# Tracksoar_v2.net
KiCad netlist of a schematic drawn in EAGLE
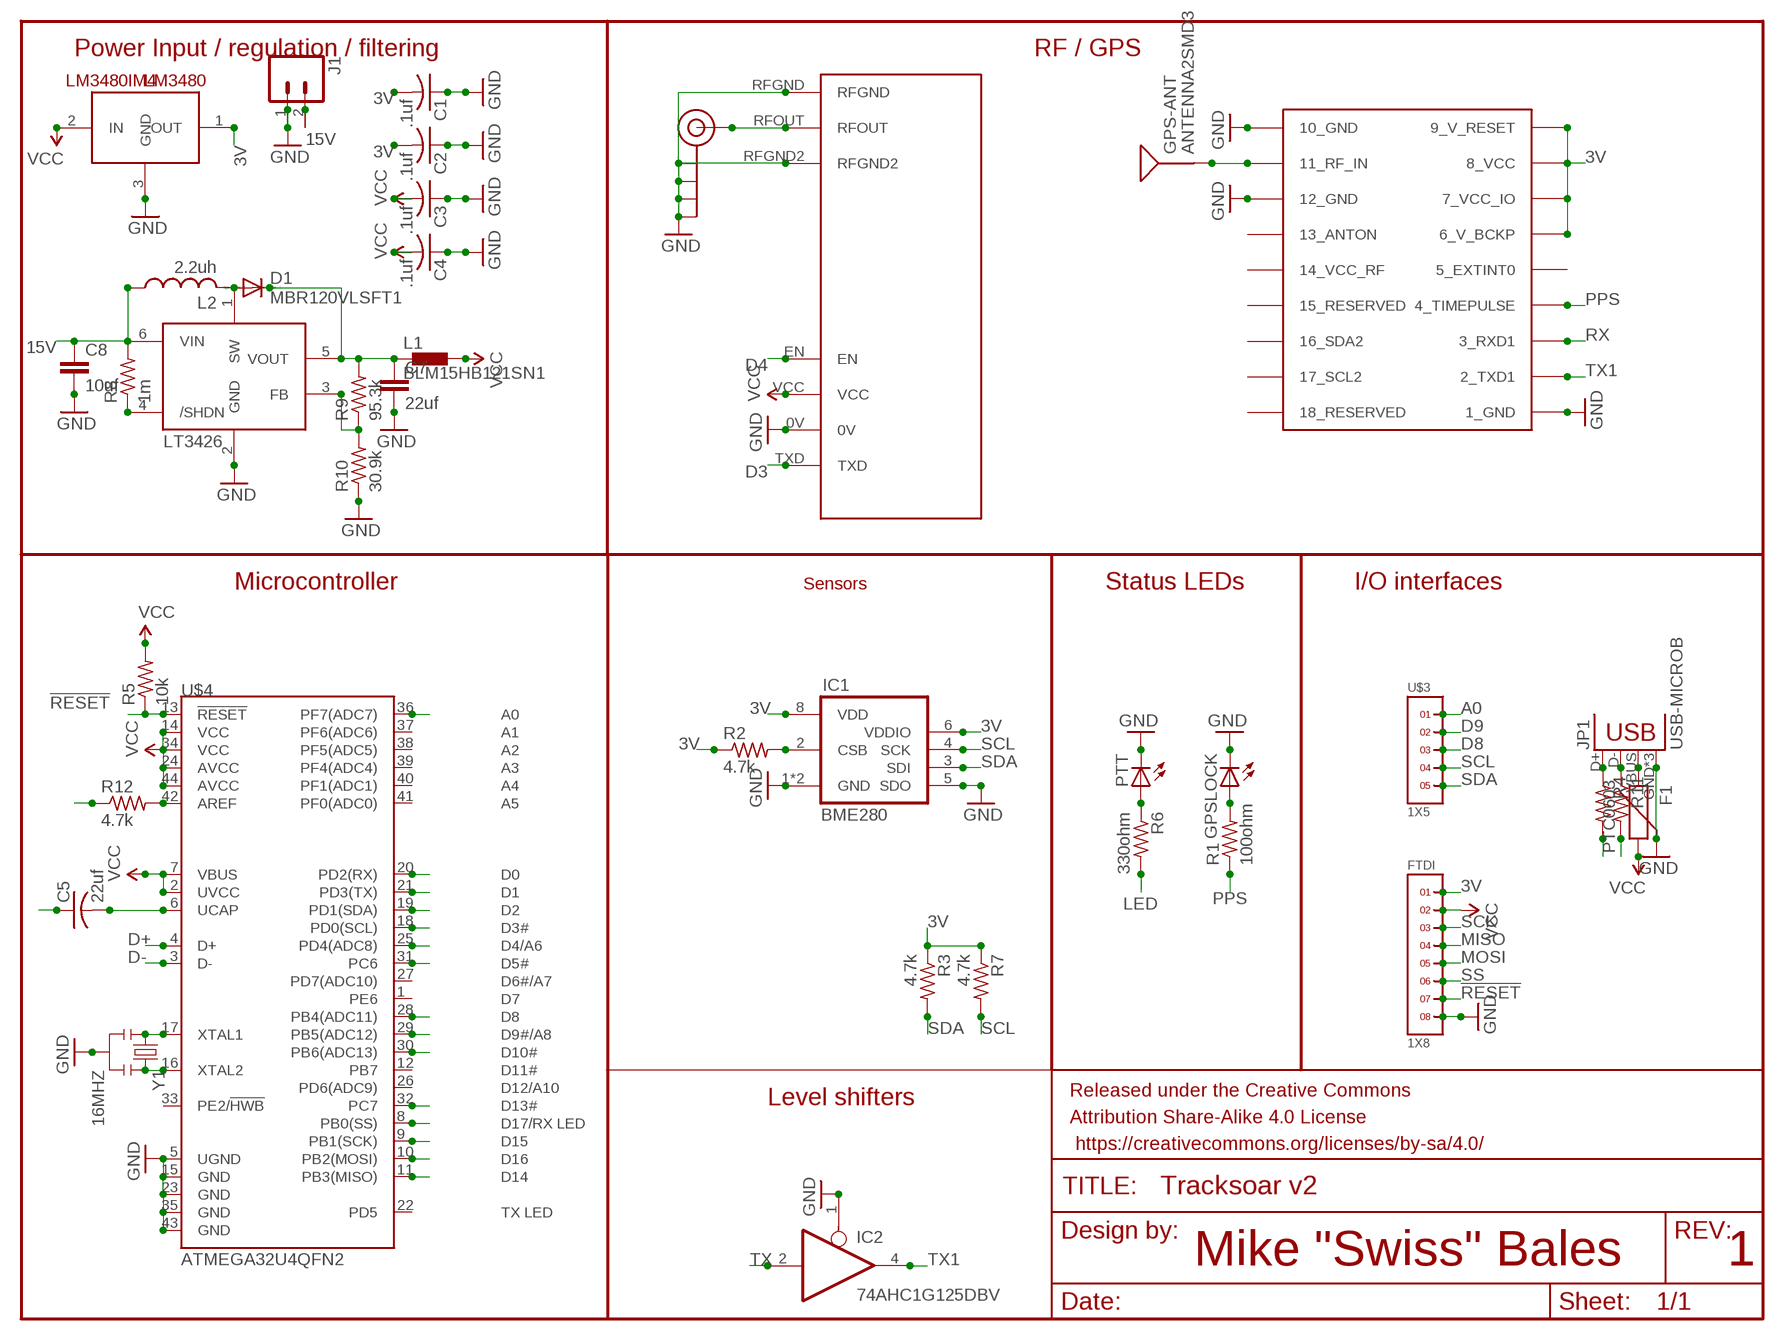
[diagram p0: schematic, sheet 1]

(export (version "E")
  (design (tool "Eeschema 10.0.6"))
  (components
    (comp (ref "C1")
      (value ".1uf")
      (footprint "eagle-import:C0402")
      (libsource (lib "eagle-import") (part "C-USC0402"))
    )
    (comp (ref "C2")
      (value ".1uf")
      (footprint "eagle-import:C0402")
      (libsource (lib "eagle-import") (part "C-USC0402"))
    )
    (comp (ref "C3")
      (value ".1uf")
      (footprint "eagle-import:C0402")
      (libsource (lib "eagle-import") (part "C-USC0402"))
    )
    (comp (ref "C4")
      (value ".1uf")
      (footprint "eagle-import:C0402")
      (libsource (lib "eagle-import") (part "C-USC0402"))
    )
    (comp (ref "C5")
      (value "22uf")
      (footprint "eagle-import:C0402")
      (libsource (lib "eagle-import") (part "rcl_C-USC0402"))
    )
    (comp (ref "C7")
      (value "22uf")
      (footprint "eagle-import:0805")
      (libsource (lib "eagle-import") (part "CAP0805"))
    )
    (comp (ref "C8")
      (value "10uf")
      (footprint "eagle-import:0805")
      (libsource (lib "eagle-import") (part "CAP0805"))
    )
    (comp (ref "D1")
      (value "MBR120VLSFT1")
      (footprint "eagle-import:SOD123")
      (libsource (lib "eagle-import") (part "DIODE-SOD123"))
    )
    (comp (ref "F1")
      (value "PTC0603")
      (footprint "eagle-import:0603")
      (libsource (lib "eagle-import") (part "PTC0603"))
    )
    (comp (ref "FRAME1")
      (value "FRAME-LETTER")
      (footprint "eagle-import:CREATIVE_COMMONS")
      (libsource (lib "eagle-import") (part "FRAME-LETTER"))
    )
    (comp (ref "FTDI")
      (value "1X8")
      (footprint "eagle-import:1X8")
      (libsource (lib "eagle-import") (part "1X8"))
    )
    (comp (ref "GPS-ANT")
      (value "ANTENNA2SMD3")
      (footprint "eagle-import:ANTENNA-CHIP4")
      (libsource (lib "eagle-import") (part "ANTENNA2SMD3"))
    )
    (comp (ref "GPSLOCK")
      (value "LEDCHIP-LED0603")
      (footprint "eagle-import:CHIP-LED0603")
      (libsource (lib "eagle-import") (part "LEDCHIP-LED0603"))
    )
    (comp (ref "IC1")
      (value "BME280")
      (footprint "eagle-import:BME280")
      (libsource (lib "eagle-import") (part "BME280"))
    )
    (comp (ref "IC2")
      (value "74AHC1G125DBV")
      (footprint "eagle-import:SOT23-5")
      (libsource (lib "eagle-import") (part "741G125DBVAHC"))
    )
    (comp (ref "J$1")
      (value "SMA_EDGE")
      (footprint "eagle-import:SMA-EDGE")
      (libsource (lib "eagle-import") (part "SMA_EDGE"))
    )
    (comp (ref "J1")
      (value "M02JST-PTH-2")
      (footprint "eagle-import:JST-2-PTH")
      (libsource (lib "eagle-import") (part "M02JST-PTH-2"))
    )
    (comp (ref "JP1")
      (value "USB-MICROB")
      (footprint "eagle-import:USB-MICROB")
      (libsource (lib "eagle-import") (part "USB-MICROB"))
    )
    (comp (ref "L1")
      (value "BLM15HB121SN1")
      (footprint "eagle-import:0402")
      (libsource (lib "eagle-import") (part "BLM15HB121SN1"))
    )
    (comp (ref "L2")
      (value "2.2uh")
      (footprint "eagle-import:L1812")
      (libsource (lib "eagle-import") (part "L-USL1812"))
    )
    (comp (ref "LM3480")
      (value "LM3480IM4")
      (footprint "eagle-import:SOT23-3")
      (libsource (lib "eagle-import") (part "LM3480IM4"))
    )
    (comp (ref "LT3426")
      (value "LT3426")
      (footprint "eagle-import:SOT23-6")
      (libsource (lib "eagle-import") (part "LT3426"))
    )
    (comp (ref "PTT")
      (value "LEDCHIP-LED0603")
      (footprint "eagle-import:CHIP-LED0603")
      (libsource (lib "eagle-import") (part "LEDCHIP-LED0603"))
    )
    (comp (ref "R1")
      (value "100ohm")
      (footprint "eagle-import:R0402")
      (libsource (lib "eagle-import") (part "R-US_R0402"))
    )
    (comp (ref "R2")
      (value "4.7k")
      (footprint "eagle-import:R0402")
      (libsource (lib "eagle-import") (part "R-US_R0402"))
    )
    (comp (ref "R3")
      (value "4.7k")
      (footprint "eagle-import:R0402")
      (libsource (lib "eagle-import") (part "R-US_R0402"))
    )
    (comp (ref "R4")
      (value "R-US_R0402")
      (footprint "eagle-import:R0402")
      (libsource (lib "eagle-import") (part "R-US_R0402"))
    )
    (comp (ref "R5")
      (value "10k")
      (footprint "eagle-import:R0402")
      (libsource (lib "eagle-import") (part "R-US_R0402"))
    )
    (comp (ref "R6")
      (value "330ohm")
      (footprint "eagle-import:R0402")
      (libsource (lib "eagle-import") (part "R-US_R0402"))
    )
    (comp (ref "R7")
      (value "4.7k")
      (footprint "eagle-import:R0402")
      (libsource (lib "eagle-import") (part "R-US_R0402"))
    )
    (comp (ref "R8")
      (value "1m")
      (footprint "eagle-import:R0402")
      (libsource (lib "eagle-import") (part "R-US_R0402"))
    )
    (comp (ref "R9")
      (value "95.3k")
      (footprint "eagle-import:R0402")
      (libsource (lib "eagle-import") (part "R-US_R0402"))
    )
    (comp (ref "R10")
      (value "30.9k")
      (footprint "eagle-import:R0402")
      (libsource (lib "eagle-import") (part "R-US_R0402"))
    )
    (comp (ref "R11")
      (value "R-US_R0402")
      (footprint "eagle-import:R0402")
      (libsource (lib "eagle-import") (part "R-US_R0402"))
    )
    (comp (ref "R12")
      (value "4.7k")
      (footprint "eagle-import:R0402")
      (libsource (lib "eagle-import") (part "R-US_R0402"))
    )
    (comp (ref "U$1")
      (value "UBLOX_MAX")
      (footprint "eagle-import:UBLOX_MAX")
      (libsource (lib "eagle-import") (part "UBLOX_MAX"))
    )
    (comp (ref "U$2")
      (value "RADIOMETRIX-HX1")
      (footprint "eagle-import:RADIOMETRIX-HX1")
      (libsource (lib "eagle-import") (part "RADIOMETRIX-HX1"))
    )
    (comp (ref "U$3")
      (value "1X5")
      (footprint "eagle-import:1X5")
      (libsource (lib "eagle-import") (part "1X5"))
    )
    (comp (ref "U$4")
      (value "ATMEGA32U4QFN2")
      (footprint "eagle-import:QFN-44-NOPAD")
      (libsource (lib "eagle-import") (part "ATMEGA32U4QFN2"))
    )
    (comp (ref "Y1")
      (value "16MHZ")
      (footprint "eagle-import:RESONATOR-SMD")
      (libsource (lib "eagle-import") (part "RESONATOR16MHZ"))
    )
  )
  (nets
    (net (code "1") (name "/3V") (class "Default")
      (node (ref "C1") (pin "2") (pinfunction "2_2") (pintype "passive"))
      (node (ref "C2") (pin "2") (pinfunction "2_2") (pintype "passive"))
      (node (ref "FTDI") (pin "1") (pinfunction "1_1") (pintype "bidirectional"))
      (node (ref "IC1") (pin "6") (pinfunction "VDDIO_6") (pintype "power_in"))
      (node (ref "IC1") (pin "8") (pinfunction "VDD_8") (pintype "power_in"))
      (node (ref "LM3480") (pin "1") (pinfunction "OUT_1") (pintype "bidirectional"))
      (node (ref "R2") (pin "1") (pinfunction "1_1") (pintype "passive"))
      (node (ref "R3") (pin "1") (pinfunction "1_1") (pintype "passive"))
      (node (ref "R7") (pin "1") (pinfunction "1_1") (pintype "passive"))
      (node (ref "U$1") (pin "6_V_BCKP") (pinfunction "6_V_BCKP_6_V_BCKP") (pintype "bidirectional"))
      (node (ref "U$1") (pin "7_VCC_IO") (pinfunction "7_VCC_IO_7_VCC_IO") (pintype "power_in"))
      (node (ref "U$1") (pin "8_VCC") (pinfunction "8_VCC_8_VCC") (pintype "power_in"))
      (node (ref "U$1") (pin "9_V_RESET") (pinfunction "9_V_RESET_9_V_RESET") (pintype "power_in"))
    )
    (net (code "2") (name "/15V") (class "Default")
      (node (ref "C8") (pin "1") (pinfunction "1_1") (pintype "passive"))
      (node (ref "J1") (pin "2") (pinfunction "2_2") (pintype "passive"))
      (node (ref "L2") (pin "1") (pinfunction "1_1") (pintype "passive"))
      (node (ref "LT3426") (pin "6") (pinfunction "VIN_6") (pintype "input"))
      (node (ref "R12") (pin "1") (pinfunction "1_1") (pintype "passive"))
      (node (ref "R8") (pin "2") (pinfunction "2_2") (pintype "passive"))
    )
    (net (code "3") (name "/A0") (class "Default")
      (node (ref "U$3") (pin "1") (pinfunction "1_1") (pintype "bidirectional"))
      (node (ref "U$4") (pin "36") (pinfunction "PF7(ADC7)_36") (pintype "bidirectional"))
    )
    (net (code "4") (name "/D+") (class "Default")
      (node (ref "R4") (pin "2") (pinfunction "2_2") (pintype "passive"))
      (node (ref "U$4") (pin "4") (pinfunction "D+_4") (pintype "bidirectional"))
    )
    (net (code "5") (name "/D-") (class "Default")
      (node (ref "R11") (pin "2") (pinfunction "2_2") (pintype "passive"))
      (node (ref "U$4") (pin "3") (pinfunction "D-_3") (pintype "bidirectional"))
    )
    (net (code "6") (name "/D3") (class "Default")
      (node (ref "U$2") (pin "TXD") (pinfunction "TXD_TXD") (pintype "bidirectional"))
      (node (ref "U$4") (pin "30") (pinfunction "PB6(ADC13)_30") (pintype "bidirectional"))
    )
    (net (code "7") (name "/D4") (class "Default")
      (node (ref "U$2") (pin "EN") (pinfunction "EN_EN") (pintype "bidirectional"))
      (node (ref "U$4") (pin "25") (pinfunction "PD4(ADC8)_25") (pintype "bidirectional"))
    )
    (net (code "8") (name "/D8") (class "Default")
      (node (ref "U$3") (pin "3") (pinfunction "3_3") (pintype "bidirectional"))
      (node (ref "U$4") (pin "28") (pinfunction "PB4(ADC11)_28") (pintype "bidirectional"))
    )
    (net (code "9") (name "/D9") (class "Default")
      (node (ref "U$3") (pin "2") (pinfunction "2_2") (pintype "bidirectional"))
      (node (ref "U$4") (pin "29") (pinfunction "PB5(ADC12)_29") (pintype "bidirectional"))
    )
    (net (code "10") (name "/LED") (class "Default")
      (node (ref "R6") (pin "2") (pinfunction "2_2") (pintype "passive"))
      (node (ref "U$4") (pin "31") (pinfunction "PC6_31") (pintype "bidirectional"))
    )
    (net (code "11") (name "/MISO") (class "Default")
      (node (ref "FTDI") (pin "4") (pinfunction "4_4") (pintype "bidirectional"))
      (node (ref "U$4") (pin "11") (pinfunction "PB3(MISO)_11") (pintype "bidirectional"))
    )
    (net (code "12") (name "/MOSI") (class "Default")
      (node (ref "FTDI") (pin "5") (pinfunction "5_5") (pintype "bidirectional"))
      (node (ref "U$4") (pin "10") (pinfunction "PB2(MOSI)_10") (pintype "bidirectional"))
    )
    (net (code "13") (name "/PPS") (class "Default")
      (node (ref "R1") (pin "1") (pinfunction "1_1") (pintype "passive"))
      (node (ref "U$1") (pin "4_TIMEPULSE") (pinfunction "4_TIMEPULSE_4_TIMEPULSE") (pintype "bidirectional"))
    )
    (net (code "14") (name "/RX") (class "Default")
      (node (ref "U$1") (pin "3_RXD1") (pinfunction "3_RXD1_3_RXD1") (pintype "bidirectional"))
      (node (ref "U$4") (pin "21") (pinfunction "PD3(TX)_21") (pintype "bidirectional"))
    )
    (net (code "15") (name "/SCK") (class "Default")
      (node (ref "FTDI") (pin "3") (pinfunction "3_3") (pintype "bidirectional"))
      (node (ref "U$4") (pin "9") (pinfunction "PB1(SCK)_9") (pintype "bidirectional"))
    )
    (net (code "16") (name "/SCL") (class "Default")
      (node (ref "IC1") (pin "4") (pinfunction "SCK_4") (pintype "bidirectional"))
      (node (ref "R7") (pin "2") (pinfunction "2_2") (pintype "passive"))
      (node (ref "U$3") (pin "4") (pinfunction "4_4") (pintype "bidirectional"))
      (node (ref "U$4") (pin "18") (pinfunction "PD0(SCL)_18") (pintype "bidirectional"))
    )
    (net (code "17") (name "/SDA") (class "Default")
      (node (ref "IC1") (pin "3") (pinfunction "SDI_3") (pintype "bidirectional"))
      (node (ref "R3") (pin "2") (pinfunction "2_2") (pintype "passive"))
      (node (ref "U$3") (pin "5") (pinfunction "5_5") (pintype "bidirectional"))
      (node (ref "U$4") (pin "19") (pinfunction "PD1(SDA)_19") (pintype "bidirectional"))
    )
    (net (code "18") (name "/SS") (class "Default")
      (node (ref "FTDI") (pin "6") (pinfunction "6_6") (pintype "bidirectional"))
      (node (ref "U$4") (pin "8") (pinfunction "PB0(SS)_8") (pintype "bidirectional"))
    )
    (net (code "19") (name "/TX") (class "Default")
      (node (ref "IC2") (pin "2") (pinfunction "I_2") (pintype "input"))
      (node (ref "U$4") (pin "20") (pinfunction "PD2(RX)_20") (pintype "bidirectional"))
    )
    (net (code "20") (name "/TX1") (class "Default")
      (node (ref "IC2") (pin "4") (pinfunction "O_4") (pintype "tri_state"))
      (node (ref "U$1") (pin "2_TXD1") (pinfunction "2_TXD1_2_TXD1") (pintype "bidirectional"))
    )
    (net (code "21") (name "/~{RESET}") (class "Default")
      (node (ref "FTDI") (pin "7") (pinfunction "7_7") (pintype "bidirectional"))
      (node (ref "R5") (pin "1") (pinfunction "1_1") (pintype "passive"))
      (node (ref "U$4") (pin "13") (pinfunction "~{RESET}_13") (pintype "bidirectional"))
    )
    (net (code "22") (name "GND") (class "Default")
      (node (ref "C1") (pin "1") (pinfunction "1_1") (pintype "passive"))
      (node (ref "C2") (pin "1") (pinfunction "1_1") (pintype "passive"))
      (node (ref "C3") (pin "1") (pinfunction "1_1") (pintype "passive"))
      (node (ref "C4") (pin "1") (pinfunction "1_1") (pintype "passive"))
      (node (ref "C5") (pin "1") (pinfunction "1_1") (pintype "passive"))
      (node (ref "C7") (pin "2") (pinfunction "2_2") (pintype "passive"))
      (node (ref "C8") (pin "2") (pinfunction "2_2") (pintype "passive"))
      (node (ref "FTDI") (pin "8") (pinfunction "8_8") (pintype "bidirectional"))
      (node (ref "GPSLOCK") (pin "C") (pinfunction "C_C") (pintype "passive"))
      (node (ref "IC1") (pin "1") (pinfunction "GND_1") (pintype "power_in"))
      (node (ref "IC1") (pin "5") (pinfunction "SDO_5") (pintype "input"))
      (node (ref "IC1") (pin "7") (pinfunction "GND_7") (pintype "power_in"))
      (node (ref "IC2") (pin "1") (pinfunction "OE_1") (pintype "input"))
      (node (ref "J$1") (pin "GND@0") (pinfunction "GND_GND@0") (pintype "bidirectional"))
      (node (ref "J$1") (pin "GND@1") (pinfunction "GND_GND@1") (pintype "bidirectional"))
      (node (ref "J$1") (pin "GND@2") (pinfunction "GND_GND@2") (pintype "bidirectional"))
      (node (ref "J$1") (pin "GND@3") (pinfunction "GND_GND@3") (pintype "bidirectional"))
      (node (ref "J1") (pin "1") (pinfunction "1_1") (pintype "passive"))
      (node (ref "JP1") (pin "GND") (pinfunction "GND_GND") (pintype "bidirectional"))
      (node (ref "JP1") (pin "MT1") (pinfunction "GND_MT1") (pintype "bidirectional"))
      (node (ref "JP1") (pin "MT2") (pinfunction "GND_MT2") (pintype "bidirectional"))
      (node (ref "LM3480") (pin "3") (pinfunction "GND_3") (pintype "bidirectional"))
      (node (ref "LT3426") (pin "2") (pinfunction "GND_2") (pintype "power_in"))
      (node (ref "PTT") (pin "C") (pinfunction "C_C") (pintype "passive"))
      (node (ref "R10") (pin "1") (pinfunction "1_1") (pintype "passive"))
      (node (ref "U$1") (pin "10_GND") (pinfunction "10_GND_10_GND") (pintype "power_in"))
      (node (ref "U$1") (pin "12_GND") (pinfunction "12_GND_12_GND") (pintype "power_in"))
      (node (ref "U$1") (pin "1_GND") (pinfunction "1_GND_1_GND") (pintype "power_in"))
      (node (ref "U$2") (pin "0V") (pinfunction "0V_0V") (pintype "bidirectional"))
      (node (ref "U$2") (pin "RFGND") (pinfunction "RFGND_RFGND") (pintype "bidirectional"))
      (node (ref "U$2") (pin "RFGND2") (pinfunction "RFGND2_RFGND2") (pintype "bidirectional"))
      (node (ref "U$4") (pin "15") (pinfunction "GND_15") (pintype "bidirectional"))
      (node (ref "U$4") (pin "23") (pinfunction "GND_23") (pintype "bidirectional"))
      (node (ref "U$4") (pin "35") (pinfunction "GND_35") (pintype "bidirectional"))
      (node (ref "U$4") (pin "43") (pinfunction "GND_43") (pintype "bidirectional"))
      (node (ref "U$4") (pin "5") (pinfunction "UGND_5") (pintype "bidirectional"))
      (node (ref "Y1") (pin "2") (pinfunction "2_2") (pintype "passive"))
    )
    (net (code "23") (name "Net-(F1-Pad1)") (class "Default")
      (node (ref "F1") (pin "1") (pinfunction "1_1") (pintype "bidirectional"))
      (node (ref "JP1") (pin "VBUS") (pinfunction "VBUS_VBUS") (pintype "bidirectional"))
    )
    (net (code "24") (name "Net-(GPS-ANT-SIGNAL)") (class "Default")
      (node (ref "GPS-ANT") (pin "SIG") (pinfunction "SIGNAL_SIG") (pintype "bidirectional"))
      (node (ref "U$1") (pin "11_RF_IN") (pinfunction "11_RF_IN_11_RF_IN") (pintype "bidirectional"))
    )
    (net (code "25") (name "Net-(GPSLOCK-PadA)") (class "Default")
      (node (ref "GPSLOCK") (pin "A") (pinfunction "A_A") (pintype "passive"))
      (node (ref "R1") (pin "2") (pinfunction "2_2") (pintype "passive"))
    )
    (net (code "26") (name "Net-(IC1-CSB)") (class "Default")
      (node (ref "IC1") (pin "2") (pinfunction "CSB_2") (pintype "input"))
      (node (ref "R2") (pin "2") (pinfunction "2_2") (pintype "passive"))
    )
    (net (code "27") (name "Net-(J$1-SIGNAL)") (class "Default")
      (node (ref "J$1") (pin "SIG") (pinfunction "SIGNAL_SIG") (pintype "bidirectional"))
      (node (ref "U$2") (pin "RFOUT") (pinfunction "RFOUT_RFOUT") (pintype "bidirectional"))
    )
    (net (code "28") (name "Net-(JP1-PadD+)") (class "Default")
      (node (ref "JP1") (pin "D+") (pinfunction "D+_D+") (pintype "bidirectional"))
      (node (ref "R4") (pin "1") (pinfunction "1_1") (pintype "passive"))
    )
    (net (code "29") (name "Net-(JP1-PadD-)") (class "Default")
      (node (ref "JP1") (pin "D-") (pinfunction "D-_D-") (pintype "bidirectional"))
      (node (ref "R11") (pin "1") (pinfunction "1_1") (pintype "passive"))
    )
    (net (code "30") (name "Net-(LT3426-FB)") (class "Default")
      (node (ref "LT3426") (pin "3") (pinfunction "FB_3") (pintype "input"))
      (node (ref "R10") (pin "2") (pinfunction "2_2") (pintype "passive"))
      (node (ref "R9") (pin "1") (pinfunction "1_1") (pintype "passive"))
    )
    (net (code "31") (name "Net-(LT3426-SW)") (class "Default")
      (node (ref "D1") (pin "A") (pinfunction "A_A") (pintype "passive"))
      (node (ref "L2") (pin "2") (pinfunction "2_2") (pintype "passive"))
      (node (ref "LT3426") (pin "1") (pinfunction "SW_1") (pintype "output"))
    )
    (net (code "32") (name "Net-(LT3426-VOUT)") (class "Default")
      (node (ref "C7") (pin "1") (pinfunction "1_1") (pintype "passive"))
      (node (ref "D1") (pin "C") (pinfunction "C_C") (pintype "passive"))
      (node (ref "L1") (pin "1") (pinfunction "1_1") (pintype "passive"))
      (node (ref "LT3426") (pin "5") (pinfunction "VOUT_5") (pintype "output"))
      (node (ref "R9") (pin "2") (pinfunction "2_2") (pintype "passive"))
    )
    (net (code "33") (name "Net-(LT3426-{slash}SHDN)") (class "Default")
      (node (ref "LT3426") (pin "4") (pinfunction "/SHDN_4") (pintype "input"))
      (node (ref "R8") (pin "1") (pinfunction "1_1") (pintype "passive"))
    )
    (net (code "34") (name "Net-(PTT-PadA)") (class "Default")
      (node (ref "PTT") (pin "A") (pinfunction "A_A") (pintype "passive"))
      (node (ref "R6") (pin "1") (pinfunction "1_1") (pintype "passive"))
    )
    (net (code "35") (name "Net-(U$4-AREF)") (class "Default")
      (node (ref "R12") (pin "2") (pinfunction "2_2") (pintype "passive"))
      (node (ref "U$4") (pin "42") (pinfunction "AREF_42") (pintype "bidirectional"))
    )
    (net (code "36") (name "Net-(U$4-UCAP)") (class "Default")
      (node (ref "C5") (pin "2") (pinfunction "2_2") (pintype "passive"))
      (node (ref "U$4") (pin "6") (pinfunction "UCAP_6") (pintype "bidirectional"))
    )
    (net (code "37") (name "Net-(U$4-XTAL1)") (class "Default")
      (node (ref "U$4") (pin "17") (pinfunction "XTAL1_17") (pintype "bidirectional"))
      (node (ref "Y1") (pin "1") (pinfunction "1_1") (pintype "passive"))
    )
    (net (code "38") (name "Net-(U$4-XTAL2)") (class "Default")
      (node (ref "U$4") (pin "16") (pinfunction "XTAL2_16") (pintype "bidirectional"))
      (node (ref "Y1") (pin "3") (pinfunction "3_3") (pintype "passive"))
    )
    (net (code "39") (name "VCC") (class "Default")
      (node (ref "C3") (pin "2") (pinfunction "2_2") (pintype "passive"))
      (node (ref "C4") (pin "2") (pinfunction "2_2") (pintype "passive"))
      (node (ref "F1") (pin "2") (pinfunction "2_2") (pintype "bidirectional"))
      (node (ref "FTDI") (pin "2") (pinfunction "2_2") (pintype "bidirectional"))
      (node (ref "L1") (pin "2") (pinfunction "2_2") (pintype "passive"))
      (node (ref "LM3480") (pin "2") (pinfunction "IN_2") (pintype "bidirectional"))
      (node (ref "R5") (pin "2") (pinfunction "2_2") (pintype "passive"))
      (node (ref "U$2") (pin "VCC") (pinfunction "VCC_VCC") (pintype "bidirectional"))
      (node (ref "U$4") (pin "14") (pinfunction "VCC_14") (pintype "bidirectional"))
      (node (ref "U$4") (pin "2") (pinfunction "UVCC_2") (pintype "bidirectional"))
      (node (ref "U$4") (pin "24") (pinfunction "AVCC_24") (pintype "bidirectional"))
      (node (ref "U$4") (pin "34") (pinfunction "VCC_34") (pintype "bidirectional"))
      (node (ref "U$4") (pin "44") (pinfunction "AVCC_44") (pintype "bidirectional"))
      (node (ref "U$4") (pin "7") (pinfunction "VBUS_7") (pintype "bidirectional"))
    )
    (net (code "40") (name "unconnected-(U$1-Pad5_EXTINT0)") (class "Default")
      (node (ref "U$1") (pin "5_EXTINT0") (pinfunction "5_EXTINT0_5_EXTINT0") (pintype "bidirectional"))
    )
    (net (code "41") (name "unconnected-(U$1-Pad13_ANTON)") (class "Default")
      (node (ref "U$1") (pin "13_ANTON") (pinfunction "13_ANTON_13_ANTON") (pintype "bidirectional"))
    )
    (net (code "42") (name "unconnected-(U$1-Pad14_VCC_RF)") (class "Default")
      (node (ref "U$1") (pin "14_VCC_RF") (pinfunction "14_VCC_RF_14_VCC_RF") (pintype "bidirectional"))
    )
    (net (code "43") (name "unconnected-(U$1-Pad15_RESERVED)") (class "Default")
      (node (ref "U$1") (pin "15_RESERVED") (pinfunction "15_RESERVED_15_RESERVED") (pintype "bidirectional"))
    )
    (net (code "44") (name "unconnected-(U$1-Pad16_SDA2)") (class "Default")
      (node (ref "U$1") (pin "16_SDA2") (pinfunction "16_SDA2_16_SDA2") (pintype "bidirectional"))
    )
    (net (code "45") (name "unconnected-(U$1-Pad17_SCL2)") (class "Default")
      (node (ref "U$1") (pin "17_SCL2") (pinfunction "17_SCL2_17_SCL2") (pintype "bidirectional"))
    )
    (net (code "46") (name "unconnected-(U$1-Pad18_RESERVED)") (class "Default")
      (node (ref "U$1") (pin "18_RESERVED") (pinfunction "18_RESERVED_18_RESERVED") (pintype "bidirectional"))
    )
    (net (code "47") (name "unconnected-(U$4-PB7-Pad12)") (class "Default")
      (node (ref "U$4") (pin "12") (pinfunction "PB7_12") (pintype "bidirectional"))
    )
    (net (code "48") (name "unconnected-(U$4-PC7-Pad32)") (class "Default")
      (node (ref "U$4") (pin "32") (pinfunction "PC7_32") (pintype "bidirectional"))
    )
    (net (code "49") (name "unconnected-(U$4-PD5-Pad22)") (class "Default")
      (node (ref "U$4") (pin "22") (pinfunction "PD5_22") (pintype "bidirectional"))
    )
    (net (code "50") (name "unconnected-(U$4-PD6(ADC9)-Pad26)") (class "Default")
      (node (ref "U$4") (pin "26") (pinfunction "PD6(ADC9)_26") (pintype "bidirectional"))
    )
    (net (code "51") (name "unconnected-(U$4-PD7(ADC10)-Pad27)") (class "Default")
      (node (ref "U$4") (pin "27") (pinfunction "PD7(ADC10)_27") (pintype "bidirectional"))
    )
    (net (code "52") (name "unconnected-(U$4-PE2{slash}~{HWB}-Pad33)") (class "Default")
      (node (ref "U$4") (pin "33") (pinfunction "PE2/~{HWB}_33") (pintype "bidirectional"))
    )
    (net (code "53") (name "unconnected-(U$4-PE6-Pad1)") (class "Default")
      (node (ref "U$4") (pin "1") (pinfunction "PE6_1") (pintype "bidirectional"))
    )
    (net (code "54") (name "unconnected-(U$4-PF0(ADC0)-Pad41)") (class "Default")
      (node (ref "U$4") (pin "41") (pinfunction "PF0(ADC0)_41") (pintype "bidirectional"))
    )
    (net (code "55") (name "unconnected-(U$4-PF1(ADC1)-Pad40)") (class "Default")
      (node (ref "U$4") (pin "40") (pinfunction "PF1(ADC1)_40") (pintype "bidirectional"))
    )
    (net (code "56") (name "unconnected-(U$4-PF4(ADC4)-Pad39)") (class "Default")
      (node (ref "U$4") (pin "39") (pinfunction "PF4(ADC4)_39") (pintype "bidirectional"))
    )
    (net (code "57") (name "unconnected-(U$4-PF5(ADC5)-Pad38)") (class "Default")
      (node (ref "U$4") (pin "38") (pinfunction "PF5(ADC5)_38") (pintype "bidirectional"))
    )
    (net (code "58") (name "unconnected-(U$4-PF6(ADC6)-Pad37)") (class "Default")
      (node (ref "U$4") (pin "37") (pinfunction "PF6(ADC6)_37") (pintype "bidirectional"))
    )
  )
)
